# me433-2021-1.net
KiCad netlist of a schematic drawn in EAGLE
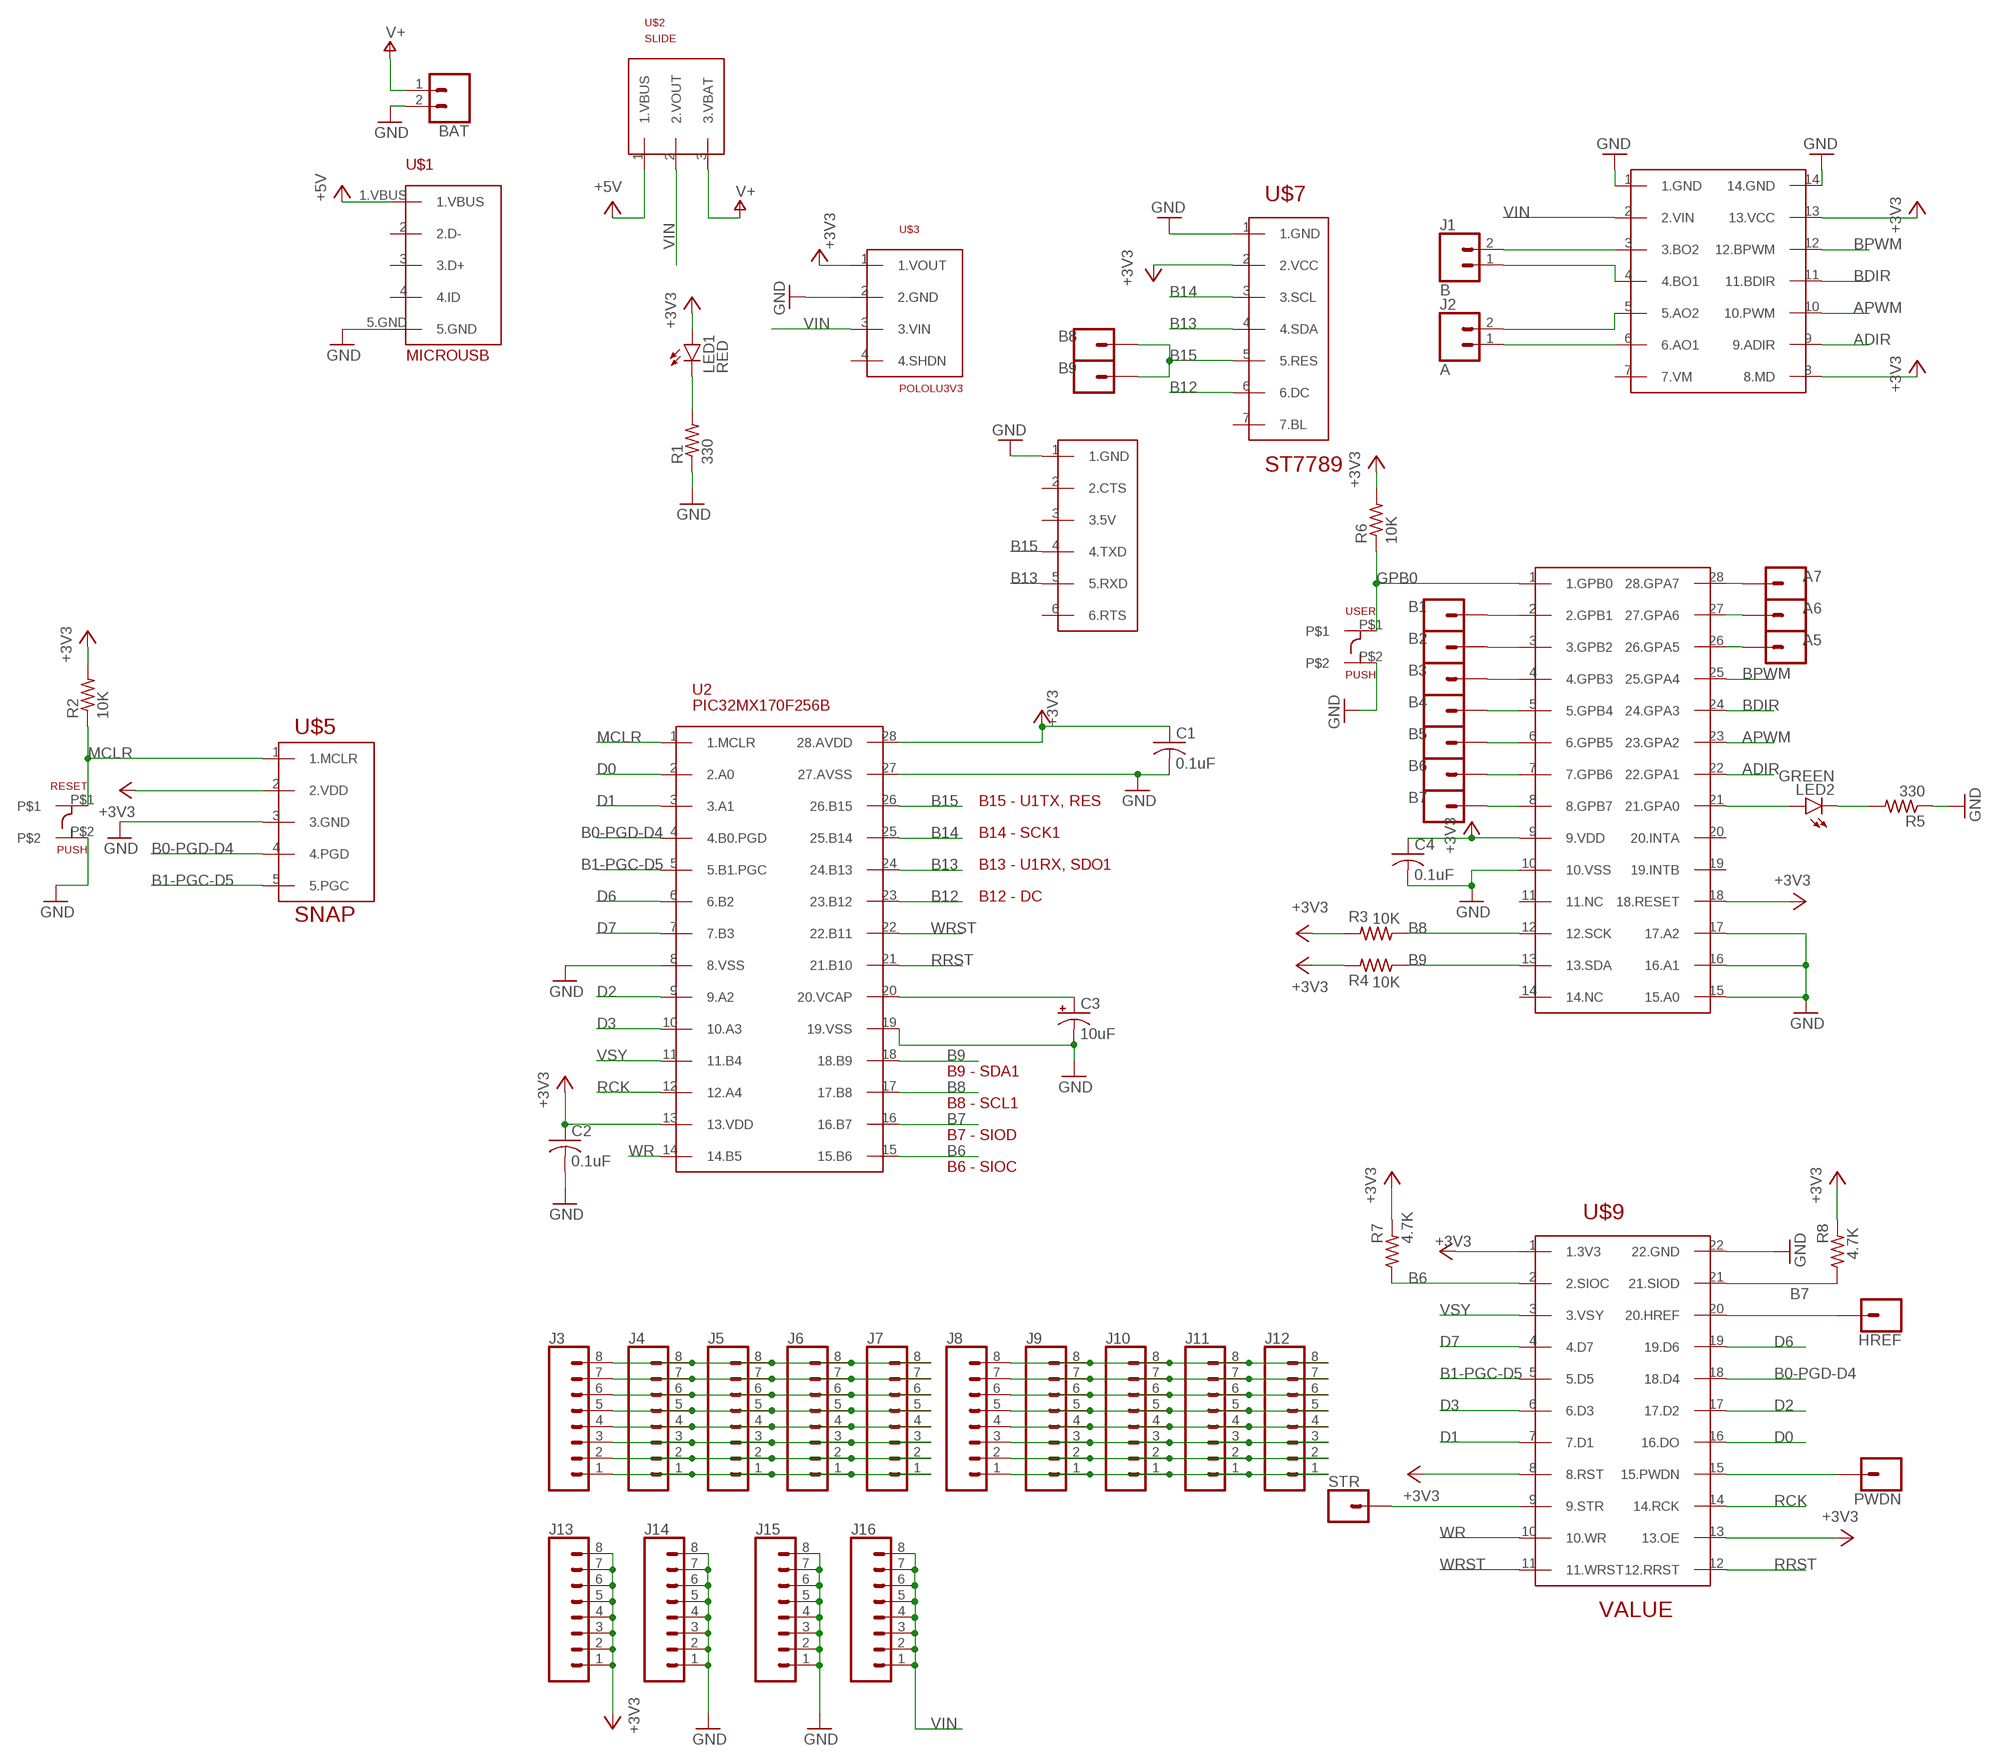
[diagram p0: schematic, sheet 1]

(export (version "E")
  (design (tool "Eeschema 10.0.6"))
  (components
    (comp (ref "A5")
      (value "CONN_01")
      (footprint "eagle-import:1X01")
      (libsource (lib "eagle-import") (part "CONN_01"))
    )
    (comp (ref "A6")
      (value "CONN_01")
      (footprint "eagle-import:1X01")
      (libsource (lib "eagle-import") (part "CONN_01"))
    )
    (comp (ref "A7")
      (value "CONN_01")
      (footprint "eagle-import:1X01")
      (libsource (lib "eagle-import") (part "CONN_01"))
    )
    (comp (ref "B1")
      (value "CONN_01")
      (footprint "eagle-import:1X01")
      (libsource (lib "eagle-import") (part "CONN_01"))
    )
    (comp (ref "B2")
      (value "CONN_01")
      (footprint "eagle-import:1X01")
      (libsource (lib "eagle-import") (part "CONN_01"))
    )
    (comp (ref "B3")
      (value "CONN_01")
      (footprint "eagle-import:1X01")
      (libsource (lib "eagle-import") (part "CONN_01"))
    )
    (comp (ref "B4")
      (value "CONN_01")
      (footprint "eagle-import:1X01")
      (libsource (lib "eagle-import") (part "CONN_01"))
    )
    (comp (ref "B5")
      (value "CONN_01")
      (footprint "eagle-import:1X01")
      (libsource (lib "eagle-import") (part "CONN_01"))
    )
    (comp (ref "B6")
      (value "CONN_01")
      (footprint "eagle-import:1X01")
      (libsource (lib "eagle-import") (part "CONN_01"))
    )
    (comp (ref "B7")
      (value "CONN_01")
      (footprint "eagle-import:1X01")
      (libsource (lib "eagle-import") (part "CONN_01"))
    )
    (comp (ref "B8")
      (value "CONN_01")
      (footprint "eagle-import:1X01")
      (libsource (lib "eagle-import") (part "CONN_01"))
    )
    (comp (ref "B9")
      (value "CONN_01")
      (footprint "eagle-import:1X01")
      (libsource (lib "eagle-import") (part "CONN_01"))
    )
    (comp (ref "BAT")
      (value "CONN_02")
      (footprint "eagle-import:1X02")
      (libsource (lib "eagle-import") (part "CONN_02"))
    )
    (comp (ref "C1")
      (value "0.1uF")
      (footprint "eagle-import:C025-030X050")
      (libsource (lib "eagle-import") (part "C-US025-030X050"))
    )
    (comp (ref "C2")
      (value "0.1uF")
      (footprint "eagle-import:C025-030X050")
      (libsource (lib "eagle-import") (part "C-US025-030X050"))
    )
    (comp (ref "C3")
      (value "10uF")
      (footprint "eagle-import:B45181B")
      (libsource (lib "eagle-import") (part "CPOL-USB45181B"))
    )
    (comp (ref "C4")
      (value "0.1uF")
      (footprint "eagle-import:C025-030X050")
      (libsource (lib "eagle-import") (part "C-US025-030X050"))
    )
    (comp (ref "HREF")
      (value "CONN_01")
      (footprint "eagle-import:1X01")
      (libsource (lib "eagle-import") (part "CONN_01"))
    )
    (comp (ref "J1")
      (value "B")
      (footprint "eagle-import:1X02")
      (libsource (lib "eagle-import") (part "CONN_02"))
    )
    (comp (ref "J2")
      (value "A")
      (footprint "eagle-import:1X02")
      (libsource (lib "eagle-import") (part "CONN_02"))
    )
    (comp (ref "J3")
      (value "CONN_08\"")
      (footprint "eagle-import:1X08")
      (libsource (lib "eagle-import") (part "CONN_08{dblquote}"))
    )
    (comp (ref "J4")
      (value "CONN_08\"")
      (footprint "eagle-import:1X08")
      (libsource (lib "eagle-import") (part "CONN_08{dblquote}"))
    )
    (comp (ref "J5")
      (value "CONN_08\"")
      (footprint "eagle-import:1X08")
      (libsource (lib "eagle-import") (part "CONN_08{dblquote}"))
    )
    (comp (ref "J6")
      (value "CONN_08\"")
      (footprint "eagle-import:1X08")
      (libsource (lib "eagle-import") (part "CONN_08{dblquote}"))
    )
    (comp (ref "J7")
      (value "CONN_08\"")
      (footprint "eagle-import:1X08")
      (libsource (lib "eagle-import") (part "CONN_08{dblquote}"))
    )
    (comp (ref "J8")
      (value "CONN_08\"")
      (footprint "eagle-import:1X08")
      (libsource (lib "eagle-import") (part "CONN_08{dblquote}"))
    )
    (comp (ref "J9")
      (value "CONN_08\"")
      (footprint "eagle-import:1X08")
      (libsource (lib "eagle-import") (part "CONN_08{dblquote}"))
    )
    (comp (ref "J10")
      (value "CONN_08\"")
      (footprint "eagle-import:1X08")
      (libsource (lib "eagle-import") (part "CONN_08{dblquote}"))
    )
    (comp (ref "J11")
      (value "CONN_08\"")
      (footprint "eagle-import:1X08")
      (libsource (lib "eagle-import") (part "CONN_08{dblquote}"))
    )
    (comp (ref "J12")
      (value "CONN_08\"")
      (footprint "eagle-import:1X08")
      (libsource (lib "eagle-import") (part "CONN_08{dblquote}"))
    )
    (comp (ref "J13")
      (value "CONN_08\"")
      (footprint "eagle-import:1X08")
      (libsource (lib "eagle-import") (part "CONN_08{dblquote}"))
    )
    (comp (ref "J14")
      (value "CONN_08\"")
      (footprint "eagle-import:1X08")
      (libsource (lib "eagle-import") (part "CONN_08{dblquote}"))
    )
    (comp (ref "J15")
      (value "CONN_08\"")
      (footprint "eagle-import:1X08")
      (libsource (lib "eagle-import") (part "CONN_08{dblquote}"))
    )
    (comp (ref "J16")
      (value "CONN_08\"")
      (footprint "eagle-import:1X08")
      (libsource (lib "eagle-import") (part "CONN_08{dblquote}"))
    )
    (comp (ref "LED1")
      (value "RED")
      (footprint "eagle-import:LED3MM")
      (libsource (lib "eagle-import") (part "LED3MM"))
    )
    (comp (ref "LED2")
      (value "GREEN")
      (footprint "eagle-import:LED3MM")
      (libsource (lib "eagle-import") (part "LED3MM"))
    )
    (comp (ref "PWDN")
      (value "CONN_01")
      (footprint "eagle-import:1X01")
      (libsource (lib "eagle-import") (part "CONN_01"))
    )
    (comp (ref "R1")
      (value "330")
      (footprint "eagle-import:0207_10")
      (libsource (lib "eagle-import") (part "R-US_0207/10"))
    )
    (comp (ref "R2")
      (value "10K")
      (footprint "eagle-import:0207_10")
      (libsource (lib "eagle-import") (part "R-US_0207/10"))
    )
    (comp (ref "R3")
      (value "10K")
      (footprint "eagle-import:0207_10")
      (libsource (lib "eagle-import") (part "R-US_0207/10"))
    )
    (comp (ref "R4")
      (value "10K")
      (footprint "eagle-import:0207_10")
      (libsource (lib "eagle-import") (part "R-US_0207/10"))
    )
    (comp (ref "R5")
      (value "330")
      (footprint "eagle-import:0207_10")
      (libsource (lib "eagle-import") (part "R-US_0207/10"))
    )
    (comp (ref "R6")
      (value "10K")
      (footprint "eagle-import:0207_10")
      (libsource (lib "eagle-import") (part "R-US_0207/10"))
    )
    (comp (ref "R7")
      (value "4.7K")
      (footprint "eagle-import:0207_10")
      (libsource (lib "eagle-import") (part "R-US_0207/10"))
    )
    (comp (ref "R8")
      (value "4.7K")
      (footprint "eagle-import:0207_10")
      (libsource (lib "eagle-import") (part "R-US_0207/10"))
    )
    (comp (ref "RESET")
      (value "PUSH")
      (footprint "eagle-import:PUSH")
      (libsource (lib "eagle-import") (part "PUSH"))
    )
    (comp (ref "STR")
      (value "CONN_01")
      (footprint "eagle-import:1X01")
      (libsource (lib "eagle-import") (part "CONN_01"))
    )
    (comp (ref "U$1")
      (value "MICROUSB")
      (footprint "eagle-import:MICROUSB")
      (libsource (lib "eagle-import") (part "MICROUSB"))
    )
    (comp (ref "U$2")
      (value "SLIDE")
      (footprint "eagle-import:SLIDE")
      (libsource (lib "eagle-import") (part "SLIDE"))
    )
    (comp (ref "U$3")
      (value "POLOLU3V3")
      (footprint "eagle-import:POLOLU3V3")
      (libsource (lib "eagle-import") (part "POLOLU3V3"))
    )
    (comp (ref "U$4")
      (value "DRV8835")
      (footprint "eagle-import:DRV8835")
      (libsource (lib "eagle-import") (part "DRV8835"))
    )
    (comp (ref "U$5")
      (value "SNAP")
      (footprint "eagle-import:SNAP")
      (libsource (lib "eagle-import") (part "SNAP"))
    )
    (comp (ref "U$6")
      (value "CP2104_FRIEND")
      (footprint "eagle-import:CP2104_FRIEND")
      (libsource (lib "eagle-import") (part "CP2104_FRIEND"))
    )
    (comp (ref "U$7")
      (value "ST7789")
      (footprint "eagle-import:ST7789")
      (libsource (lib "eagle-import") (part "ST7789"))
    )
    (comp (ref "U$8")
      (value "MCP23017")
      (footprint "eagle-import:DIL28-3")
      (libsource (lib "eagle-import") (part "MCP23017"))
    )
    (comp (ref "U$9")
      (value "OV7670FIFO")
      (footprint "eagle-import:OV7670FIFO")
      (libsource (lib "eagle-import") (part "OV7670FIFO"))
    )
    (comp (ref "U2")
      (value "PIC32MX170F256B")
      (footprint "eagle-import:DIL28-3")
      (libsource (lib "eagle-import") (part "PIC32MX170F256B"))
    )
    (comp (ref "USER")
      (value "PUSH")
      (footprint "eagle-import:PUSH")
      (libsource (lib "eagle-import") (part "PUSH"))
    )
  )
  (nets
    (net (code "1") (name "+3V3") (class "Default")
      (node (ref "C1") (pin "1") (pinfunction "1_1") (pintype "passive"))
      (node (ref "C2") (pin "1") (pinfunction "1_1") (pintype "passive"))
      (node (ref "C4") (pin "1") (pinfunction "1_1") (pintype "passive"))
      (node (ref "J13") (pin "1") (pinfunction "1_1") (pintype "passive"))
      (node (ref "J13") (pin "2") (pinfunction "2_2") (pintype "passive"))
      (node (ref "J13") (pin "3") (pinfunction "3_3") (pintype "passive"))
      (node (ref "J13") (pin "4") (pinfunction "4_4") (pintype "passive"))
      (node (ref "J13") (pin "5") (pinfunction "5_5") (pintype "passive"))
      (node (ref "J13") (pin "6") (pinfunction "6_6") (pintype "passive"))
      (node (ref "J13") (pin "7") (pinfunction "7_7") (pintype "passive"))
      (node (ref "J13") (pin "8") (pinfunction "8_8") (pintype "passive"))
      (node (ref "LED1") (pin "A") (pinfunction "A_A") (pintype "passive"))
      (node (ref "R2") (pin "2") (pinfunction "2_2") (pintype "passive"))
      (node (ref "R3") (pin "2") (pinfunction "2_2") (pintype "passive"))
      (node (ref "R4") (pin "2") (pinfunction "2_2") (pintype "passive"))
      (node (ref "R6") (pin "2") (pinfunction "2_2") (pintype "passive"))
      (node (ref "R7") (pin "2") (pinfunction "2_2") (pintype "passive"))
      (node (ref "R8") (pin "2") (pinfunction "2_2") (pintype "passive"))
      (node (ref "U$3") (pin "1") (pinfunction "1.VOUT_1") (pintype "bidirectional"))
      (node (ref "U$4") (pin "13") (pinfunction "13.VCC_13") (pintype "bidirectional"))
      (node (ref "U$4") (pin "8") (pinfunction "8.MD_8") (pintype "bidirectional"))
      (node (ref "U$5") (pin "2") (pinfunction "2.VDD_2") (pintype "bidirectional"))
      (node (ref "U$7") (pin "2") (pinfunction "2.VCC_2") (pintype "bidirectional"))
      (node (ref "U$8") (pin "18") (pinfunction "18.RESET_18") (pintype "bidirectional"))
      (node (ref "U$8") (pin "9") (pinfunction "9.VDD_9") (pintype "bidirectional"))
      (node (ref "U$9") (pin "1") (pinfunction "1.3V3_1") (pintype "bidirectional"))
      (node (ref "U$9") (pin "13") (pinfunction "13.OE_13") (pintype "bidirectional"))
      (node (ref "U$9") (pin "8") (pinfunction "8.RST_8") (pintype "bidirectional"))
      (node (ref "U2") (pin "13") (pinfunction "13.VDD_13") (pintype "bidirectional"))
      (node (ref "U2") (pin "28") (pinfunction "28.AVDD_28") (pintype "bidirectional"))
    )
    (net (code "2") (name "+5V") (class "Default")
      (node (ref "U$1") (pin "1.VBUS") (pinfunction "1.VBUS_1.VBUS") (pintype "bidirectional"))
      (node (ref "U$2") (pin "1") (pinfunction "1.VBUS_1") (pintype "bidirectional"))
    )
    (net (code "3") (name "/ADIR") (class "Default")
      (node (ref "U$4") (pin "9") (pinfunction "9.ADIR_9") (pintype "bidirectional"))
      (node (ref "U$8") (pin "22") (pinfunction "22.GPA1_22") (pintype "bidirectional"))
    )
    (net (code "4") (name "/APWM") (class "Default")
      (node (ref "U$4") (pin "10") (pinfunction "10.PWM_10") (pintype "bidirectional"))
      (node (ref "U$8") (pin "23") (pinfunction "23.GPA2_23") (pintype "bidirectional"))
    )
    (net (code "5") (name "/B0-PGD-D4") (class "Default")
      (node (ref "U$5") (pin "4") (pinfunction "4.PGD_4") (pintype "bidirectional"))
      (node (ref "U$9") (pin "18") (pinfunction "18.D4_18") (pintype "bidirectional"))
      (node (ref "U2") (pin "4") (pinfunction "4.B0.PGD_4") (pintype "bidirectional"))
    )
    (net (code "6") (name "/B1-PGC-D5") (class "Default")
      (node (ref "U$5") (pin "5") (pinfunction "5.PGC_5") (pintype "bidirectional"))
      (node (ref "U$9") (pin "5") (pinfunction "5.D5_5") (pintype "bidirectional"))
      (node (ref "U2") (pin "5") (pinfunction "5.B1.PGC_5") (pintype "bidirectional"))
    )
    (net (code "7") (name "/B6") (class "Default")
      (node (ref "R7") (pin "1") (pinfunction "1_1") (pintype "passive"))
      (node (ref "U$9") (pin "2") (pinfunction "2.SIOC_2") (pintype "bidirectional"))
      (node (ref "U2") (pin "15") (pinfunction "15.B6_15") (pintype "bidirectional"))
    )
    (net (code "8") (name "/B7") (class "Default")
      (node (ref "R8") (pin "1") (pinfunction "1_1") (pintype "passive"))
      (node (ref "U$9") (pin "21") (pinfunction "21.SIOD_21") (pintype "bidirectional"))
      (node (ref "U2") (pin "16") (pinfunction "16.B7_16") (pintype "bidirectional"))
    )
    (net (code "9") (name "/B8") (class "Default")
      (node (ref "R3") (pin "1") (pinfunction "1_1") (pintype "passive"))
      (node (ref "U$8") (pin "12") (pinfunction "12.SCK_12") (pintype "bidirectional"))
      (node (ref "U2") (pin "17") (pinfunction "17.B8_17") (pintype "bidirectional"))
    )
    (net (code "10") (name "/B9") (class "Default")
      (node (ref "R4") (pin "1") (pinfunction "1_1") (pintype "passive"))
      (node (ref "U$8") (pin "13") (pinfunction "13.SDA_13") (pintype "bidirectional"))
      (node (ref "U2") (pin "18") (pinfunction "18.B9_18") (pintype "bidirectional"))
    )
    (net (code "11") (name "/B12") (class "Default")
      (node (ref "U$7") (pin "6") (pinfunction "6.DC_6") (pintype "bidirectional"))
      (node (ref "U2") (pin "23") (pinfunction "23.B12_23") (pintype "bidirectional"))
    )
    (net (code "12") (name "/B13") (class "Default")
      (node (ref "U$6") (pin "5") (pinfunction "5.RXD_5") (pintype "bidirectional"))
      (node (ref "U$7") (pin "4") (pinfunction "4.SDA_4") (pintype "bidirectional"))
      (node (ref "U2") (pin "24") (pinfunction "24.B13_24") (pintype "bidirectional"))
    )
    (net (code "13") (name "/B14") (class "Default")
      (node (ref "U$7") (pin "3") (pinfunction "3.SCL_3") (pintype "bidirectional"))
      (node (ref "U2") (pin "25") (pinfunction "25.B14_25") (pintype "bidirectional"))
    )
    (net (code "14") (name "/B15") (class "Default")
      (node (ref "B8") (pin "1") (pinfunction "1_1") (pintype "passive"))
      (node (ref "B9") (pin "1") (pinfunction "1_1") (pintype "passive"))
      (node (ref "U$6") (pin "4") (pinfunction "4.TXD_4") (pintype "bidirectional"))
      (node (ref "U$7") (pin "5") (pinfunction "5.RES_5") (pintype "bidirectional"))
      (node (ref "U2") (pin "26") (pinfunction "26.B15_26") (pintype "bidirectional"))
    )
    (net (code "15") (name "/BDIR") (class "Default")
      (node (ref "U$4") (pin "11") (pinfunction "11.BDIR_11") (pintype "bidirectional"))
      (node (ref "U$8") (pin "24") (pinfunction "24.GPA3_24") (pintype "bidirectional"))
    )
    (net (code "16") (name "/BPWM") (class "Default")
      (node (ref "U$4") (pin "12") (pinfunction "12.BPWM_12") (pintype "bidirectional"))
      (node (ref "U$8") (pin "25") (pinfunction "25.GPA4_25") (pintype "bidirectional"))
    )
    (net (code "17") (name "/D0") (class "Default")
      (node (ref "U$9") (pin "16") (pinfunction "16.DO_16") (pintype "bidirectional"))
      (node (ref "U2") (pin "2") (pinfunction "2.A0_2") (pintype "bidirectional"))
    )
    (net (code "18") (name "/D1") (class "Default")
      (node (ref "U$9") (pin "7") (pinfunction "7.D1_7") (pintype "bidirectional"))
      (node (ref "U2") (pin "3") (pinfunction "3.A1_3") (pintype "bidirectional"))
    )
    (net (code "19") (name "/D2") (class "Default")
      (node (ref "U$9") (pin "17") (pinfunction "17.D2_17") (pintype "bidirectional"))
      (node (ref "U2") (pin "9") (pinfunction "9.A2_9") (pintype "bidirectional"))
    )
    (net (code "20") (name "/D3") (class "Default")
      (node (ref "U$9") (pin "6") (pinfunction "6.D3_6") (pintype "bidirectional"))
      (node (ref "U2") (pin "10") (pinfunction "10.A3_10") (pintype "bidirectional"))
    )
    (net (code "21") (name "/D6") (class "Default")
      (node (ref "U$9") (pin "19") (pinfunction "19.D6_19") (pintype "bidirectional"))
      (node (ref "U2") (pin "6") (pinfunction "6.B2_6") (pintype "bidirectional"))
    )
    (net (code "22") (name "/D7") (class "Default")
      (node (ref "U$9") (pin "4") (pinfunction "4.D7_4") (pintype "bidirectional"))
      (node (ref "U2") (pin "7") (pinfunction "7.B3_7") (pintype "bidirectional"))
    )
    (net (code "23") (name "/GPB0") (class "Default")
      (node (ref "R6") (pin "1") (pinfunction "1_1") (pintype "passive"))
      (node (ref "U$8") (pin "1") (pinfunction "1.GPB0_1") (pintype "bidirectional"))
      (node (ref "USER") (pin "P$1") (pinfunction "P$1_P$1") (pintype "bidirectional"))
    )
    (net (code "24") (name "/MCLR") (class "Default")
      (node (ref "R2") (pin "1") (pinfunction "1_1") (pintype "passive"))
      (node (ref "RESET") (pin "P$1") (pinfunction "P$1_P$1") (pintype "bidirectional"))
      (node (ref "U$5") (pin "1") (pinfunction "1.MCLR_1") (pintype "bidirectional"))
      (node (ref "U2") (pin "1") (pinfunction "1.MCLR_1") (pintype "bidirectional"))
    )
    (net (code "25") (name "/RCK") (class "Default")
      (node (ref "U$9") (pin "14") (pinfunction "14.RCK_14") (pintype "bidirectional"))
      (node (ref "U2") (pin "12") (pinfunction "12.A4_12") (pintype "bidirectional"))
    )
    (net (code "26") (name "/RRST") (class "Default")
      (node (ref "U$9") (pin "12") (pinfunction "12.RRST_12") (pintype "bidirectional"))
      (node (ref "U2") (pin "21") (pinfunction "21.B10_21") (pintype "bidirectional"))
    )
    (net (code "27") (name "/VIN") (class "Default")
      (node (ref "J16") (pin "1") (pinfunction "1_1") (pintype "passive"))
      (node (ref "J16") (pin "2") (pinfunction "2_2") (pintype "passive"))
      (node (ref "J16") (pin "3") (pinfunction "3_3") (pintype "passive"))
      (node (ref "J16") (pin "4") (pinfunction "4_4") (pintype "passive"))
      (node (ref "J16") (pin "5") (pinfunction "5_5") (pintype "passive"))
      (node (ref "J16") (pin "6") (pinfunction "6_6") (pintype "passive"))
      (node (ref "J16") (pin "7") (pinfunction "7_7") (pintype "passive"))
      (node (ref "J16") (pin "8") (pinfunction "8_8") (pintype "passive"))
      (node (ref "U$2") (pin "2") (pinfunction "2.VOUT_2") (pintype "bidirectional"))
      (node (ref "U$3") (pin "3") (pinfunction "3.VIN_3") (pintype "bidirectional"))
      (node (ref "U$4") (pin "2") (pinfunction "2.VIN_2") (pintype "bidirectional"))
    )
    (net (code "28") (name "/VSY") (class "Default")
      (node (ref "U$9") (pin "3") (pinfunction "3.VSY_3") (pintype "bidirectional"))
      (node (ref "U2") (pin "11") (pinfunction "11.B4_11") (pintype "bidirectional"))
    )
    (net (code "29") (name "/WR") (class "Default")
      (node (ref "U$9") (pin "10") (pinfunction "10.WR_10") (pintype "bidirectional"))
      (node (ref "U2") (pin "14") (pinfunction "14.B5_14") (pintype "bidirectional"))
    )
    (net (code "30") (name "/WRST") (class "Default")
      (node (ref "U$9") (pin "11") (pinfunction "11.WRST_11") (pintype "bidirectional"))
      (node (ref "U2") (pin "22") (pinfunction "22.B11_22") (pintype "bidirectional"))
    )
    (net (code "31") (name "GND") (class "Default")
      (node (ref "BAT") (pin "2") (pinfunction "2_2") (pintype "passive"))
      (node (ref "C1") (pin "2") (pinfunction "2_2") (pintype "passive"))
      (node (ref "C2") (pin "2") (pinfunction "2_2") (pintype "passive"))
      (node (ref "C3") (pin "-") (pinfunction "-_-") (pintype "passive"))
      (node (ref "C4") (pin "2") (pinfunction "2_2") (pintype "passive"))
      (node (ref "J14") (pin "1") (pinfunction "1_1") (pintype "passive"))
      (node (ref "J14") (pin "2") (pinfunction "2_2") (pintype "passive"))
      (node (ref "J14") (pin "3") (pinfunction "3_3") (pintype "passive"))
      (node (ref "J14") (pin "4") (pinfunction "4_4") (pintype "passive"))
      (node (ref "J14") (pin "5") (pinfunction "5_5") (pintype "passive"))
      (node (ref "J14") (pin "6") (pinfunction "6_6") (pintype "passive"))
      (node (ref "J14") (pin "7") (pinfunction "7_7") (pintype "passive"))
      (node (ref "J14") (pin "8") (pinfunction "8_8") (pintype "passive"))
      (node (ref "J15") (pin "1") (pinfunction "1_1") (pintype "passive"))
      (node (ref "J15") (pin "2") (pinfunction "2_2") (pintype "passive"))
      (node (ref "J15") (pin "3") (pinfunction "3_3") (pintype "passive"))
      (node (ref "J15") (pin "4") (pinfunction "4_4") (pintype "passive"))
      (node (ref "J15") (pin "5") (pinfunction "5_5") (pintype "passive"))
      (node (ref "J15") (pin "6") (pinfunction "6_6") (pintype "passive"))
      (node (ref "J15") (pin "7") (pinfunction "7_7") (pintype "passive"))
      (node (ref "J15") (pin "8") (pinfunction "8_8") (pintype "passive"))
      (node (ref "R1") (pin "1") (pinfunction "1_1") (pintype "passive"))
      (node (ref "R5") (pin "1") (pinfunction "1_1") (pintype "passive"))
      (node (ref "RESET") (pin "P$2") (pinfunction "P$2_P$2") (pintype "bidirectional"))
      (node (ref "U$1") (pin "5.GND") (pinfunction "5.GND_5.GND") (pintype "bidirectional"))
      (node (ref "U$3") (pin "2") (pinfunction "2.GND_2") (pintype "bidirectional"))
      (node (ref "U$4") (pin "1") (pinfunction "1.GND_1") (pintype "bidirectional"))
      (node (ref "U$4") (pin "14") (pinfunction "14.GND_14") (pintype "bidirectional"))
      (node (ref "U$5") (pin "3") (pinfunction "3.GND_3") (pintype "bidirectional"))
      (node (ref "U$6") (pin "1") (pinfunction "1.GND_1") (pintype "bidirectional"))
      (node (ref "U$7") (pin "1") (pinfunction "1.GND_1") (pintype "bidirectional"))
      (node (ref "U$8") (pin "10") (pinfunction "10.VSS_10") (pintype "bidirectional"))
      (node (ref "U$8") (pin "15") (pinfunction "15.A0_15") (pintype "bidirectional"))
      (node (ref "U$8") (pin "16") (pinfunction "16.A1_16") (pintype "bidirectional"))
      (node (ref "U$8") (pin "17") (pinfunction "17.A2_17") (pintype "bidirectional"))
      (node (ref "U$9") (pin "22") (pinfunction "22.GND_22") (pintype "bidirectional"))
      (node (ref "U2") (pin "19") (pinfunction "19.VSS_19") (pintype "bidirectional"))
      (node (ref "U2") (pin "27") (pinfunction "27.AVSS_27") (pintype "bidirectional"))
      (node (ref "U2") (pin "8") (pinfunction "8.VSS_8") (pintype "bidirectional"))
      (node (ref "USER") (pin "P$2") (pinfunction "P$2_P$2") (pintype "bidirectional"))
    )
    (net (code "32") (name "Net-(J3-Pad1)") (class "Default")
      (node (ref "J3") (pin "1") (pinfunction "1_1") (pintype "passive"))
      (node (ref "J4") (pin "1") (pinfunction "1_1") (pintype "passive"))
      (node (ref "J5") (pin "1") (pinfunction "1_1") (pintype "passive"))
      (node (ref "J6") (pin "1") (pinfunction "1_1") (pintype "passive"))
      (node (ref "J7") (pin "1") (pinfunction "1_1") (pintype "passive"))
    )
    (net (code "33") (name "Net-(J3-Pad2)") (class "Default")
      (node (ref "J3") (pin "2") (pinfunction "2_2") (pintype "passive"))
      (node (ref "J4") (pin "2") (pinfunction "2_2") (pintype "passive"))
      (node (ref "J5") (pin "2") (pinfunction "2_2") (pintype "passive"))
      (node (ref "J6") (pin "2") (pinfunction "2_2") (pintype "passive"))
      (node (ref "J7") (pin "2") (pinfunction "2_2") (pintype "passive"))
    )
    (net (code "34") (name "Net-(J3-Pad3)") (class "Default")
      (node (ref "J3") (pin "3") (pinfunction "3_3") (pintype "passive"))
      (node (ref "J4") (pin "3") (pinfunction "3_3") (pintype "passive"))
      (node (ref "J5") (pin "3") (pinfunction "3_3") (pintype "passive"))
      (node (ref "J6") (pin "3") (pinfunction "3_3") (pintype "passive"))
      (node (ref "J7") (pin "3") (pinfunction "3_3") (pintype "passive"))
    )
    (net (code "35") (name "Net-(J3-Pad4)") (class "Default")
      (node (ref "J3") (pin "4") (pinfunction "4_4") (pintype "passive"))
      (node (ref "J4") (pin "4") (pinfunction "4_4") (pintype "passive"))
      (node (ref "J5") (pin "4") (pinfunction "4_4") (pintype "passive"))
      (node (ref "J6") (pin "4") (pinfunction "4_4") (pintype "passive"))
      (node (ref "J7") (pin "4") (pinfunction "4_4") (pintype "passive"))
    )
    (net (code "36") (name "Net-(J3-Pad5)") (class "Default")
      (node (ref "J3") (pin "5") (pinfunction "5_5") (pintype "passive"))
      (node (ref "J4") (pin "5") (pinfunction "5_5") (pintype "passive"))
      (node (ref "J5") (pin "5") (pinfunction "5_5") (pintype "passive"))
      (node (ref "J6") (pin "5") (pinfunction "5_5") (pintype "passive"))
      (node (ref "J7") (pin "5") (pinfunction "5_5") (pintype "passive"))
    )
    (net (code "37") (name "Net-(J3-Pad6)") (class "Default")
      (node (ref "J3") (pin "6") (pinfunction "6_6") (pintype "passive"))
      (node (ref "J4") (pin "6") (pinfunction "6_6") (pintype "passive"))
      (node (ref "J5") (pin "6") (pinfunction "6_6") (pintype "passive"))
      (node (ref "J6") (pin "6") (pinfunction "6_6") (pintype "passive"))
      (node (ref "J7") (pin "6") (pinfunction "6_6") (pintype "passive"))
    )
    (net (code "38") (name "Net-(J3-Pad7)") (class "Default")
      (node (ref "J3") (pin "7") (pinfunction "7_7") (pintype "passive"))
      (node (ref "J4") (pin "7") (pinfunction "7_7") (pintype "passive"))
      (node (ref "J5") (pin "7") (pinfunction "7_7") (pintype "passive"))
      (node (ref "J6") (pin "7") (pinfunction "7_7") (pintype "passive"))
      (node (ref "J7") (pin "7") (pinfunction "7_7") (pintype "passive"))
    )
    (net (code "39") (name "Net-(J3-Pad8)") (class "Default")
      (node (ref "J3") (pin "8") (pinfunction "8_8") (pintype "passive"))
      (node (ref "J4") (pin "8") (pinfunction "8_8") (pintype "passive"))
      (node (ref "J5") (pin "8") (pinfunction "8_8") (pintype "passive"))
      (node (ref "J6") (pin "8") (pinfunction "8_8") (pintype "passive"))
      (node (ref "J7") (pin "8") (pinfunction "8_8") (pintype "passive"))
    )
    (net (code "40") (name "Net-(J10-Pad1)") (class "Default")
      (node (ref "J10") (pin "1") (pinfunction "1_1") (pintype "passive"))
      (node (ref "J11") (pin "1") (pinfunction "1_1") (pintype "passive"))
      (node (ref "J12") (pin "1") (pinfunction "1_1") (pintype "passive"))
      (node (ref "J8") (pin "1") (pinfunction "1_1") (pintype "passive"))
      (node (ref "J9") (pin "1") (pinfunction "1_1") (pintype "passive"))
    )
    (net (code "41") (name "Net-(J10-Pad2)") (class "Default")
      (node (ref "J10") (pin "2") (pinfunction "2_2") (pintype "passive"))
      (node (ref "J11") (pin "2") (pinfunction "2_2") (pintype "passive"))
      (node (ref "J12") (pin "2") (pinfunction "2_2") (pintype "passive"))
      (node (ref "J8") (pin "2") (pinfunction "2_2") (pintype "passive"))
      (node (ref "J9") (pin "2") (pinfunction "2_2") (pintype "passive"))
    )
    (net (code "42") (name "Net-(J10-Pad3)") (class "Default")
      (node (ref "J10") (pin "3") (pinfunction "3_3") (pintype "passive"))
      (node (ref "J11") (pin "3") (pinfunction "3_3") (pintype "passive"))
      (node (ref "J12") (pin "3") (pinfunction "3_3") (pintype "passive"))
      (node (ref "J8") (pin "3") (pinfunction "3_3") (pintype "passive"))
      (node (ref "J9") (pin "3") (pinfunction "3_3") (pintype "passive"))
    )
    (net (code "43") (name "Net-(J10-Pad4)") (class "Default")
      (node (ref "J10") (pin "4") (pinfunction "4_4") (pintype "passive"))
      (node (ref "J11") (pin "4") (pinfunction "4_4") (pintype "passive"))
      (node (ref "J12") (pin "4") (pinfunction "4_4") (pintype "passive"))
      (node (ref "J8") (pin "4") (pinfunction "4_4") (pintype "passive"))
      (node (ref "J9") (pin "4") (pinfunction "4_4") (pintype "passive"))
    )
    (net (code "44") (name "Net-(J10-Pad5)") (class "Default")
      (node (ref "J10") (pin "5") (pinfunction "5_5") (pintype "passive"))
      (node (ref "J11") (pin "5") (pinfunction "5_5") (pintype "passive"))
      (node (ref "J12") (pin "5") (pinfunction "5_5") (pintype "passive"))
      (node (ref "J8") (pin "5") (pinfunction "5_5") (pintype "passive"))
      (node (ref "J9") (pin "5") (pinfunction "5_5") (pintype "passive"))
    )
    (net (code "45") (name "Net-(J10-Pad6)") (class "Default")
      (node (ref "J10") (pin "6") (pinfunction "6_6") (pintype "passive"))
      (node (ref "J11") (pin "6") (pinfunction "6_6") (pintype "passive"))
      (node (ref "J12") (pin "6") (pinfunction "6_6") (pintype "passive"))
      (node (ref "J8") (pin "6") (pinfunction "6_6") (pintype "passive"))
      (node (ref "J9") (pin "6") (pinfunction "6_6") (pintype "passive"))
    )
    (net (code "46") (name "Net-(J10-Pad7)") (class "Default")
      (node (ref "J10") (pin "7") (pinfunction "7_7") (pintype "passive"))
      (node (ref "J11") (pin "7") (pinfunction "7_7") (pintype "passive"))
      (node (ref "J12") (pin "7") (pinfunction "7_7") (pintype "passive"))
      (node (ref "J8") (pin "7") (pinfunction "7_7") (pintype "passive"))
      (node (ref "J9") (pin "7") (pinfunction "7_7") (pintype "passive"))
    )
    (net (code "47") (name "Net-(J10-Pad8)") (class "Default")
      (node (ref "J10") (pin "8") (pinfunction "8_8") (pintype "passive"))
      (node (ref "J11") (pin "8") (pinfunction "8_8") (pintype "passive"))
      (node (ref "J12") (pin "8") (pinfunction "8_8") (pintype "passive"))
      (node (ref "J8") (pin "8") (pinfunction "8_8") (pintype "passive"))
      (node (ref "J9") (pin "8") (pinfunction "8_8") (pintype "passive"))
    )
    (net (code "48") (name "Net-(LED1-C)") (class "Default")
      (node (ref "LED1") (pin "K") (pinfunction "C_K") (pintype "passive"))
      (node (ref "R1") (pin "2") (pinfunction "2_2") (pintype "passive"))
    )
    (net (code "49") (name "Net-(LED2-C)") (class "Default")
      (node (ref "LED2") (pin "K") (pinfunction "C_K") (pintype "passive"))
      (node (ref "R5") (pin "2") (pinfunction "2_2") (pintype "passive"))
    )
    (net (code "50") (name "Net-(U$4-3.BO2)") (class "Default")
      (node (ref "J1") (pin "2") (pinfunction "2_2") (pintype "passive"))
      (node (ref "U$4") (pin "3") (pinfunction "3.BO2_3") (pintype "bidirectional"))
    )
    (net (code "51") (name "Net-(U$4-4.BO1)") (class "Default")
      (node (ref "J1") (pin "1") (pinfunction "1_1") (pintype "passive"))
      (node (ref "U$4") (pin "4") (pinfunction "4.BO1_4") (pintype "bidirectional"))
    )
    (net (code "52") (name "Net-(U$4-5.AO2)") (class "Default")
      (node (ref "J2") (pin "2") (pinfunction "2_2") (pintype "passive"))
      (node (ref "U$4") (pin "5") (pinfunction "5.AO2_5") (pintype "bidirectional"))
    )
    (net (code "53") (name "Net-(U$4-6.AO1)") (class "Default")
      (node (ref "J2") (pin "1") (pinfunction "1_1") (pintype "passive"))
      (node (ref "U$4") (pin "6") (pinfunction "6.AO1_6") (pintype "bidirectional"))
    )
    (net (code "54") (name "Net-(U$8-2.GPB1)") (class "Default")
      (node (ref "B1") (pin "1") (pinfunction "1_1") (pintype "passive"))
      (node (ref "U$8") (pin "2") (pinfunction "2.GPB1_2") (pintype "bidirectional"))
    )
    (net (code "55") (name "Net-(U$8-3.GPB2)") (class "Default")
      (node (ref "B2") (pin "1") (pinfunction "1_1") (pintype "passive"))
      (node (ref "U$8") (pin "3") (pinfunction "3.GPB2_3") (pintype "bidirectional"))
    )
    (net (code "56") (name "Net-(U$8-4.GPB3)") (class "Default")
      (node (ref "B3") (pin "1") (pinfunction "1_1") (pintype "passive"))
      (node (ref "U$8") (pin "4") (pinfunction "4.GPB3_4") (pintype "bidirectional"))
    )
    (net (code "57") (name "Net-(U$8-5.GPB4)") (class "Default")
      (node (ref "B4") (pin "1") (pinfunction "1_1") (pintype "passive"))
      (node (ref "U$8") (pin "5") (pinfunction "5.GPB4_5") (pintype "bidirectional"))
    )
    (net (code "58") (name "Net-(U$8-6.GPB5)") (class "Default")
      (node (ref "B5") (pin "1") (pinfunction "1_1") (pintype "passive"))
      (node (ref "U$8") (pin "6") (pinfunction "6.GPB5_6") (pintype "bidirectional"))
    )
    (net (code "59") (name "Net-(U$8-7.GPB6)") (class "Default")
      (node (ref "B6") (pin "1") (pinfunction "1_1") (pintype "passive"))
      (node (ref "U$8") (pin "7") (pinfunction "7.GPB6_7") (pintype "bidirectional"))
    )
    (net (code "60") (name "Net-(U$8-8.GPB7)") (class "Default")
      (node (ref "B7") (pin "1") (pinfunction "1_1") (pintype "passive"))
      (node (ref "U$8") (pin "8") (pinfunction "8.GPB7_8") (pintype "bidirectional"))
    )
    (net (code "61") (name "Net-(U$8-21.GPA0)") (class "Default")
      (node (ref "LED2") (pin "A") (pinfunction "A_A") (pintype "passive"))
      (node (ref "U$8") (pin "21") (pinfunction "21.GPA0_21") (pintype "bidirectional"))
    )
    (net (code "62") (name "Net-(U$8-26.GPA5)") (class "Default")
      (node (ref "A5") (pin "1") (pinfunction "1_1") (pintype "passive"))
      (node (ref "U$8") (pin "26") (pinfunction "26.GPA5_26") (pintype "bidirectional"))
    )
    (net (code "63") (name "Net-(U$8-27.GPA6)") (class "Default")
      (node (ref "A6") (pin "1") (pinfunction "1_1") (pintype "passive"))
      (node (ref "U$8") (pin "27") (pinfunction "27.GPA6_27") (pintype "bidirectional"))
    )
    (net (code "64") (name "Net-(U$8-28.GPA7)") (class "Default")
      (node (ref "A7") (pin "1") (pinfunction "1_1") (pintype "passive"))
      (node (ref "U$8") (pin "28") (pinfunction "28.GPA7_28") (pintype "bidirectional"))
    )
    (net (code "65") (name "Net-(U$9-9.STR)") (class "Default")
      (node (ref "STR") (pin "1") (pinfunction "1_1") (pintype "passive"))
      (node (ref "U$9") (pin "9") (pinfunction "9.STR_9") (pintype "bidirectional"))
    )
    (net (code "66") (name "Net-(U$9-15.PWDN)") (class "Default")
      (node (ref "PWDN") (pin "1") (pinfunction "1_1") (pintype "passive"))
      (node (ref "U$9") (pin "15") (pinfunction "15.PWDN_15") (pintype "bidirectional"))
    )
    (net (code "67") (name "Net-(U$9-20.HREF)") (class "Default")
      (node (ref "HREF") (pin "1") (pinfunction "1_1") (pintype "passive"))
      (node (ref "U$9") (pin "20") (pinfunction "20.HREF_20") (pintype "bidirectional"))
    )
    (net (code "68") (name "Net-(U2-20.VCAP)") (class "Default")
      (node (ref "C3") (pin "+") (pinfunction "+_+") (pintype "passive"))
      (node (ref "U2") (pin "20") (pinfunction "20.VCAP_20") (pintype "bidirectional"))
    )
    (net (code "69") (name "V+") (class "Default")
      (node (ref "BAT") (pin "1") (pinfunction "1_1") (pintype "passive"))
      (node (ref "U$2") (pin "3") (pinfunction "3.VBAT_3") (pintype "bidirectional"))
    )
    (net (code "70") (name "unconnected-(U$1-2.D--Pad2)") (class "Default")
      (node (ref "U$1") (pin "2") (pinfunction "2.D-_2") (pintype "bidirectional"))
    )
    (net (code "71") (name "unconnected-(U$1-3.D+-Pad3)") (class "Default")
      (node (ref "U$1") (pin "3") (pinfunction "3.D+_3") (pintype "bidirectional"))
    )
    (net (code "72") (name "unconnected-(U$1-4.ID-Pad4)") (class "Default")
      (node (ref "U$1") (pin "4") (pinfunction "4.ID_4") (pintype "bidirectional"))
    )
    (net (code "73") (name "unconnected-(U$3-4.SHDN-Pad4)") (class "Default")
      (node (ref "U$3") (pin "4") (pinfunction "4.SHDN_4") (pintype "bidirectional"))
    )
    (net (code "74") (name "unconnected-(U$4-7.VM-Pad7)") (class "Default")
      (node (ref "U$4") (pin "7") (pinfunction "7.VM_7") (pintype "bidirectional"))
    )
    (net (code "75") (name "unconnected-(U$6-2.CTS-Pad2)") (class "Default")
      (node (ref "U$6") (pin "2") (pinfunction "2.CTS_2") (pintype "bidirectional"))
    )
    (net (code "76") (name "unconnected-(U$6-3.5V-Pad3)") (class "Default")
      (node (ref "U$6") (pin "3") (pinfunction "3.5V_3") (pintype "bidirectional"))
    )
    (net (code "77") (name "unconnected-(U$6-6.RTS-Pad6)") (class "Default")
      (node (ref "U$6") (pin "6") (pinfunction "6.RTS_6") (pintype "bidirectional"))
    )
    (net (code "78") (name "unconnected-(U$7-7.BL-Pad7)") (class "Default")
      (node (ref "U$7") (pin "7") (pinfunction "7.BL_7") (pintype "bidirectional"))
    )
    (net (code "79") (name "unconnected-(U$8-11.NC-Pad11)") (class "Default")
      (node (ref "U$8") (pin "11") (pinfunction "11.NC_11") (pintype "bidirectional"))
    )
    (net (code "80") (name "unconnected-(U$8-14.NC-Pad14)") (class "Default")
      (node (ref "U$8") (pin "14") (pinfunction "14.NC_14") (pintype "bidirectional"))
    )
    (net (code "81") (name "unconnected-(U$8-19.INTB-Pad19)") (class "Default")
      (node (ref "U$8") (pin "19") (pinfunction "19.INTB_19") (pintype "bidirectional"))
    )
    (net (code "82") (name "unconnected-(U$8-20.INTA-Pad20)") (class "Default")
      (node (ref "U$8") (pin "20") (pinfunction "20.INTA_20") (pintype "bidirectional"))
    )
  )
)
